# atmel-7-segment-rtc.net
KiCad netlist of a schematic drawn in EAGLE
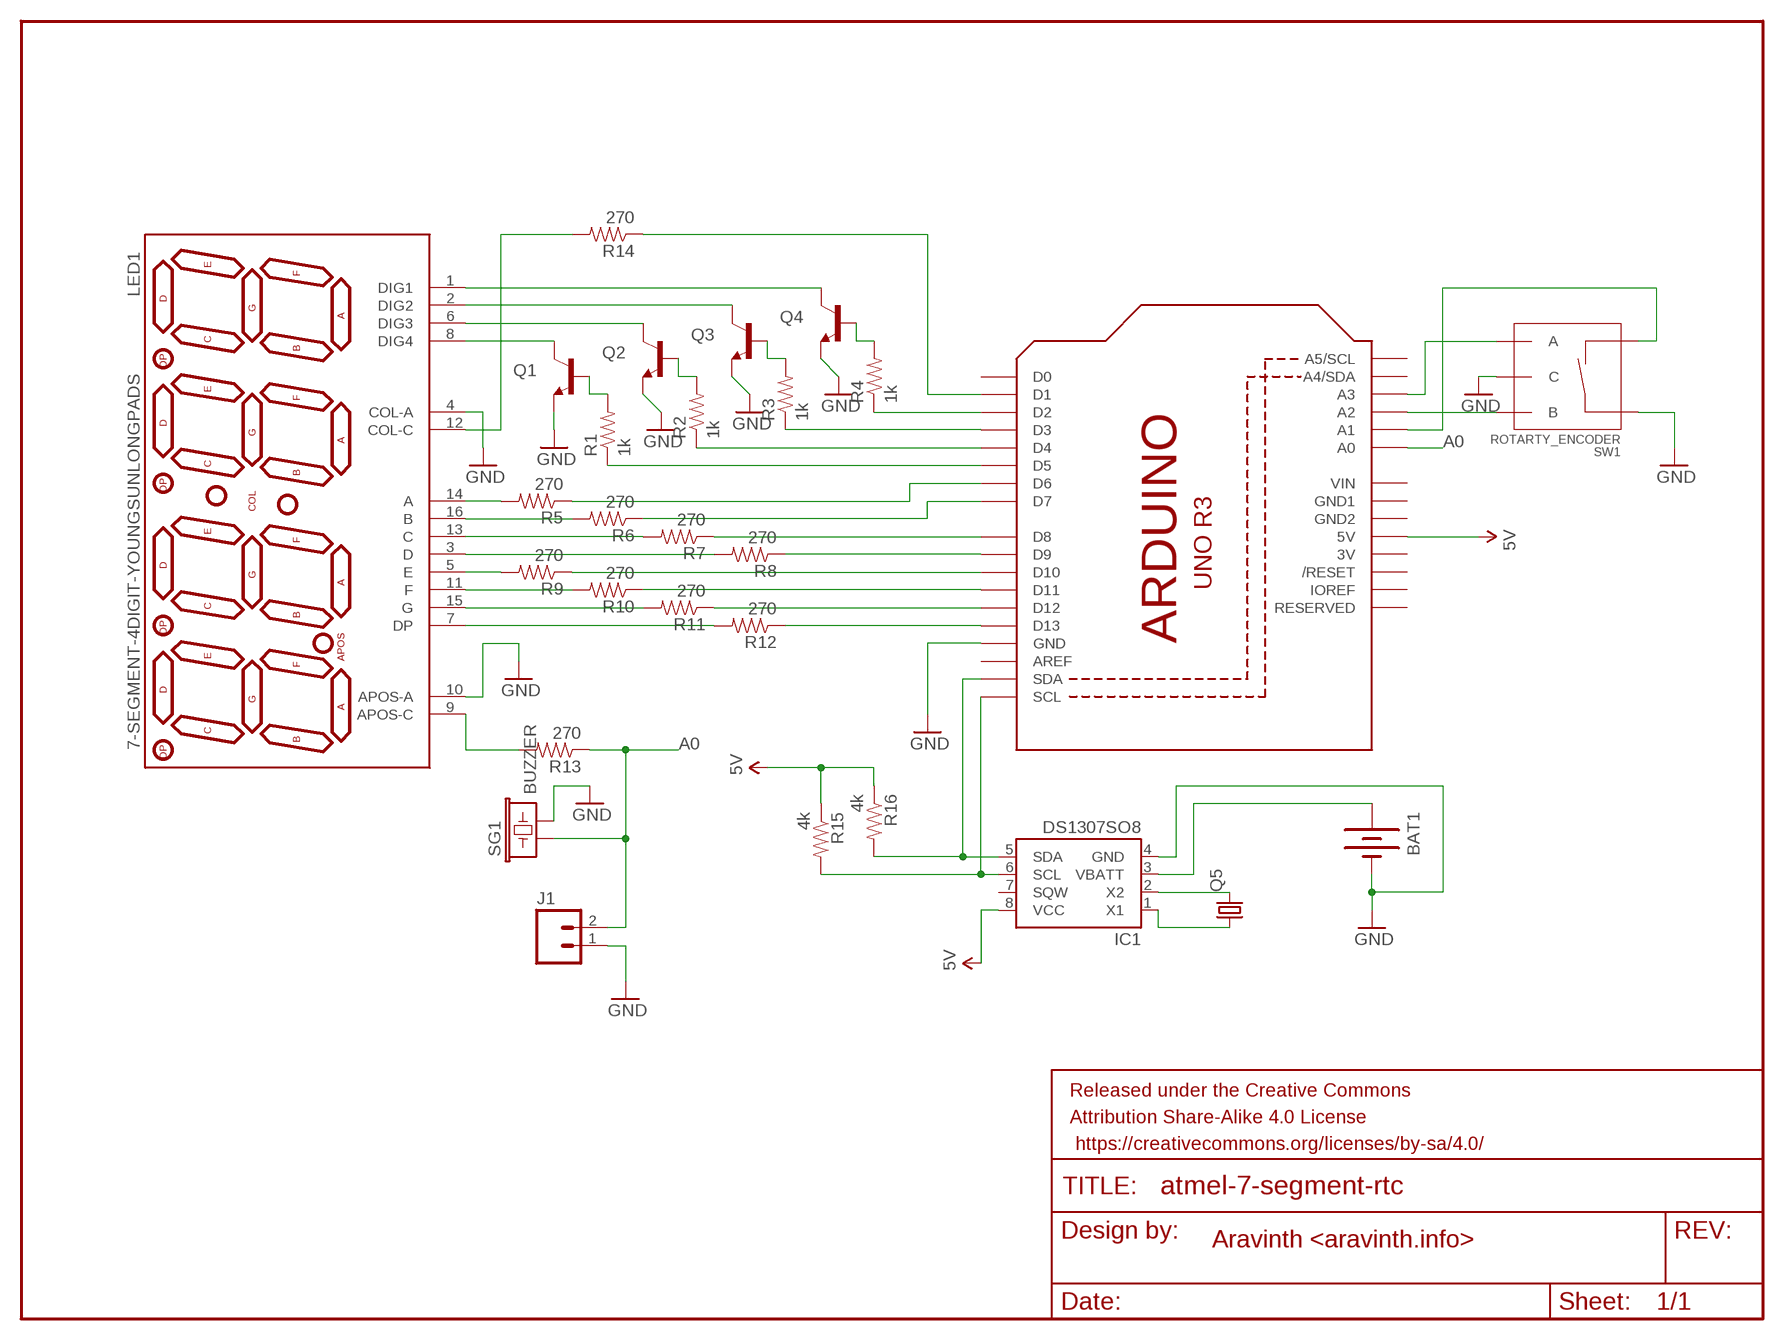
[diagram p0: schematic, sheet 1]

(export (version "E")
  (design (tool "Eeschema 10.0.6"))
  (components
    (comp (ref "ARDUINO")
      (value "ARDUINOR3-DIMENSION")
      (footprint "eagle-import:ARDUINOR3")
      (libsource (lib "eagle-import") (part "ARDUINOR3-DIMENSION"))
    )
    (comp (ref "BAT1")
      (value "BATTERY12MM")
      (footprint "eagle-import:BATTCON_12MM")
      (libsource (lib "eagle-import") (part "BATTERY12MM"))
    )
    (comp (ref "FRAME1")
      (value "FRAME-LETTER")
      (footprint "eagle-import:CREATIVE_COMMONS")
      (libsource (lib "eagle-import") (part "FRAME-LETTER"))
    )
    (comp (ref "IC1")
      (value "DS1307SO8")
      (footprint "eagle-import:SO08")
      (libsource (lib "eagle-import") (part "DS1307SO8"))
    )
    (comp (ref "J1")
      (value "M023.5MM")
      (footprint "eagle-import:SCREWTERMINAL-3.5MM-2")
      (libsource (lib "eagle-import") (part "M023.5MM"))
    )
    (comp (ref "LED1")
      (value "7-SEGMENT-4DIGIT-YOUNGSUNLONGPADS")
      (footprint "eagle-import:7-SEGMENT-4DIGIT-YOUNGSUN-LONGPADS")
      (libsource (lib "eagle-import") (part "7-SEGMENT-4DIGIT-YOUNGSUNLONGPADS"))
    )
    (comp (ref "Q1")
      (value "TRANSISTOR_NPNMMBT2222A")
      (footprint "eagle-import:SOT23-3")
      (libsource (lib "eagle-import") (part "TRANSISTOR_NPNMMBT2222A"))
    )
    (comp (ref "Q2")
      (value "TRANSISTOR_NPNMMBT2222A")
      (footprint "eagle-import:SOT23-3")
      (libsource (lib "eagle-import") (part "TRANSISTOR_NPNMMBT2222A"))
    )
    (comp (ref "Q3")
      (value "TRANSISTOR_NPNMMBT2222A")
      (footprint "eagle-import:SOT23-3")
      (libsource (lib "eagle-import") (part "TRANSISTOR_NPNMMBT2222A"))
    )
    (comp (ref "Q4")
      (value "TRANSISTOR_NPNMMBT2222A")
      (footprint "eagle-import:SOT23-3")
      (libsource (lib "eagle-import") (part "TRANSISTOR_NPNMMBT2222A"))
    )
    (comp (ref "Q5")
      (value "CRYSTALTC26H")
      (footprint "eagle-import:TC26H")
      (libsource (lib "eagle-import") (part "CRYSTALTC26H"))
    )
    (comp (ref "R1")
      (value "1k")
      (footprint "eagle-import:0805")
      (libsource (lib "eagle-import") (part "RESISTOR0805-RES"))
    )
    (comp (ref "R2")
      (value "1k")
      (footprint "eagle-import:0805")
      (libsource (lib "eagle-import") (part "RESISTOR0805-RES"))
    )
    (comp (ref "R3")
      (value "1k")
      (footprint "eagle-import:0805")
      (libsource (lib "eagle-import") (part "RESISTOR0805-RES"))
    )
    (comp (ref "R4")
      (value "1k")
      (footprint "eagle-import:0805")
      (libsource (lib "eagle-import") (part "RESISTOR0805-RES"))
    )
    (comp (ref "R5")
      (value "270")
      (footprint "eagle-import:0805")
      (libsource (lib "eagle-import") (part "RESISTOR0805-RES"))
    )
    (comp (ref "R6")
      (value "270")
      (footprint "eagle-import:0805")
      (libsource (lib "eagle-import") (part "RESISTOR0805-RES"))
    )
    (comp (ref "R7")
      (value "270")
      (footprint "eagle-import:0805")
      (libsource (lib "eagle-import") (part "RESISTOR0805-RES"))
    )
    (comp (ref "R8")
      (value "270")
      (footprint "eagle-import:0805")
      (libsource (lib "eagle-import") (part "RESISTOR0805-RES"))
    )
    (comp (ref "R9")
      (value "270")
      (footprint "eagle-import:0805")
      (libsource (lib "eagle-import") (part "RESISTOR0805-RES"))
    )
    (comp (ref "R10")
      (value "270")
      (footprint "eagle-import:0805")
      (libsource (lib "eagle-import") (part "RESISTOR0805-RES"))
    )
    (comp (ref "R11")
      (value "270")
      (footprint "eagle-import:0805")
      (libsource (lib "eagle-import") (part "RESISTOR0805-RES"))
    )
    (comp (ref "R12")
      (value "270")
      (footprint "eagle-import:0805")
      (libsource (lib "eagle-import") (part "RESISTOR0805-RES"))
    )
    (comp (ref "R13")
      (value "270")
      (footprint "eagle-import:0805")
      (libsource (lib "eagle-import") (part "RESISTOR0805-RES"))
    )
    (comp (ref "R14")
      (value "270")
      (footprint "eagle-import:0805")
      (libsource (lib "eagle-import") (part "RESISTOR0805-RES"))
    )
    (comp (ref "R15")
      (value "4k")
      (footprint "eagle-import:0805")
      (libsource (lib "eagle-import") (part "RESISTOR0805-RES"))
    )
    (comp (ref "R16")
      (value "4k")
      (footprint "eagle-import:0805")
      (libsource (lib "eagle-import") (part "RESISTOR0805-RES"))
    )
    (comp (ref "SG1")
      (value "BUZZER")
      (footprint "eagle-import:BUZZER-12MM-NS")
      (libsource (lib "eagle-import") (part "BUZZERNS"))
    )
    (comp (ref "SW1")
      (value "ROTARTY_ENCODER")
      (footprint "eagle-import:ROTARY_ENC_PLAIN")
      (libsource (lib "eagle-import") (part "ROTARTY_ENCODER"))
    )
  )
  (nets
    (net (code "1") (name "/3V") (class "Default")
      (node (ref "ARDUINO") (pin "3V") (pinfunction "3V_3V") (pintype "power_in"))
    )
    (net (code "2") (name "/A0") (class "Default")
      (node (ref "ARDUINO") (pin "A0") (pinfunction "A0_A0") (pintype "bidirectional"))
      (node (ref "J1") (pin "2") (pinfunction "2_2") (pintype "passive"))
      (node (ref "R13") (pin "1") (pinfunction "1_1") (pintype "passive"))
      (node (ref "SG1") (pin "+") (pinfunction "1_+") (pintype "passive"))
    )
    (net (code "3") (name "/GND1") (class "Default")
      (node (ref "ARDUINO") (pin "GND1") (pinfunction "GND1_GND1") (pintype "power_in"))
    )
    (net (code "4") (name "/GND2") (class "Default")
      (node (ref "ARDUINO") (pin "GND2") (pinfunction "GND2_GND2") (pintype "power_in"))
    )
    (net (code "5") (name "/VIN") (class "Default")
      (node (ref "ARDUINO") (pin "VIN") (pinfunction "VIN_VIN") (pintype "power_in"))
    )
    (net (code "6") (name "5V") (class "Default")
      (node (ref "ARDUINO") (pin "5V") (pinfunction "5V_5V") (pintype "power_in"))
      (node (ref "IC1") (pin "8") (pinfunction "VCC_8") (pintype "bidirectional"))
      (node (ref "R15") (pin "1") (pinfunction "1_1") (pintype "passive"))
      (node (ref "R16") (pin "1") (pinfunction "1_1") (pintype "passive"))
    )
    (net (code "7") (name "GND") (class "Default")
      (node (ref "ARDUINO") (pin "GND") (pinfunction "GND_GND") (pintype "power_in"))
      (node (ref "BAT1") (pin "GND") (pinfunction "-_GND") (pintype "power_in"))
      (node (ref "IC1") (pin "4") (pinfunction "GND_4") (pintype "bidirectional"))
      (node (ref "J1") (pin "1") (pinfunction "1_1") (pintype "passive"))
      (node (ref "LED1") (pin "10") (pinfunction "APOS-A_10") (pintype "bidirectional"))
      (node (ref "LED1") (pin "4") (pinfunction "COL-A_4") (pintype "bidirectional"))
      (node (ref "Q1") (pin "2") (pinfunction "E_2") (pintype "passive"))
      (node (ref "Q2") (pin "2") (pinfunction "E_2") (pintype "passive"))
      (node (ref "Q3") (pin "2") (pinfunction "E_2") (pintype "passive"))
      (node (ref "Q4") (pin "2") (pinfunction "E_2") (pintype "passive"))
      (node (ref "SG1") (pin "-") (pinfunction "2_-") (pintype "passive"))
      (node (ref "SW1") (pin "C") (pinfunction "C_C") (pintype "bidirectional"))
      (node (ref "SW1") (pin "SW+") (pinfunction "SW+_SW+") (pintype "bidirectional"))
    )
    (net (code "8") (name "Net-(ARDUINO-PadA1)") (class "Default")
      (node (ref "ARDUINO") (pin "A1") (pinfunction "A1_A1") (pintype "bidirectional"))
      (node (ref "SW1") (pin "SW-") (pinfunction "SW-_SW-") (pintype "bidirectional"))
    )
    (net (code "9") (name "Net-(ARDUINO-PadA2)") (class "Default")
      (node (ref "ARDUINO") (pin "A2") (pinfunction "A2_A2") (pintype "bidirectional"))
      (node (ref "SW1") (pin "B") (pinfunction "B_B") (pintype "bidirectional"))
    )
    (net (code "10") (name "Net-(ARDUINO-PadA3)") (class "Default")
      (node (ref "ARDUINO") (pin "A3") (pinfunction "A3_A3") (pintype "bidirectional"))
      (node (ref "SW1") (pin "A") (pinfunction "A_A") (pintype "bidirectional"))
    )
    (net (code "11") (name "Net-(ARDUINO-PadD1)") (class "Default")
      (node (ref "ARDUINO") (pin "D1") (pinfunction "D1_D1") (pintype "bidirectional"))
      (node (ref "R14") (pin "1") (pinfunction "1_1") (pintype "passive"))
    )
    (net (code "12") (name "Net-(ARDUINO-PadD2)") (class "Default")
      (node (ref "ARDUINO") (pin "D2") (pinfunction "D2_D2") (pintype "bidirectional"))
      (node (ref "R4") (pin "1") (pinfunction "1_1") (pintype "passive"))
    )
    (net (code "13") (name "Net-(ARDUINO-PadD3)") (class "Default")
      (node (ref "ARDUINO") (pin "D3") (pinfunction "D3_D3") (pintype "bidirectional"))
      (node (ref "R3") (pin "1") (pinfunction "1_1") (pintype "passive"))
    )
    (net (code "14") (name "Net-(ARDUINO-PadD4)") (class "Default")
      (node (ref "ARDUINO") (pin "D4") (pinfunction "D4_D4") (pintype "bidirectional"))
      (node (ref "R2") (pin "1") (pinfunction "1_1") (pintype "passive"))
    )
    (net (code "15") (name "Net-(ARDUINO-PadD5)") (class "Default")
      (node (ref "ARDUINO") (pin "D5") (pinfunction "D5_D5") (pintype "bidirectional"))
      (node (ref "R1") (pin "1") (pinfunction "1_1") (pintype "passive"))
    )
    (net (code "16") (name "Net-(ARDUINO-PadD6)") (class "Default")
      (node (ref "ARDUINO") (pin "D6") (pinfunction "D6_D6") (pintype "bidirectional"))
      (node (ref "R5") (pin "1") (pinfunction "1_1") (pintype "passive"))
    )
    (net (code "17") (name "Net-(ARDUINO-PadD7)") (class "Default")
      (node (ref "ARDUINO") (pin "D7") (pinfunction "D7_D7") (pintype "bidirectional"))
      (node (ref "R6") (pin "1") (pinfunction "1_1") (pintype "passive"))
    )
    (net (code "18") (name "Net-(ARDUINO-PadD8)") (class "Default")
      (node (ref "ARDUINO") (pin "D8") (pinfunction "D8_D8") (pintype "bidirectional"))
      (node (ref "R7") (pin "1") (pinfunction "1_1") (pintype "passive"))
    )
    (net (code "19") (name "Net-(ARDUINO-PadD9)") (class "Default")
      (node (ref "ARDUINO") (pin "D9") (pinfunction "D9_D9") (pintype "bidirectional"))
      (node (ref "R8") (pin "1") (pinfunction "1_1") (pintype "passive"))
    )
    (net (code "20") (name "Net-(ARDUINO-PadD10)") (class "Default")
      (node (ref "ARDUINO") (pin "D10") (pinfunction "D10_D10") (pintype "bidirectional"))
      (node (ref "R9") (pin "1") (pinfunction "1_1") (pintype "passive"))
    )
    (net (code "21") (name "Net-(ARDUINO-PadD11)") (class "Default")
      (node (ref "ARDUINO") (pin "D11") (pinfunction "D11_D11") (pintype "bidirectional"))
      (node (ref "R10") (pin "1") (pinfunction "1_1") (pintype "passive"))
    )
    (net (code "22") (name "Net-(ARDUINO-PadD12)") (class "Default")
      (node (ref "ARDUINO") (pin "D12") (pinfunction "D12_D12") (pintype "bidirectional"))
      (node (ref "R11") (pin "1") (pinfunction "1_1") (pintype "passive"))
    )
    (net (code "23") (name "Net-(ARDUINO-PadD13)") (class "Default")
      (node (ref "ARDUINO") (pin "D13") (pinfunction "D13_D13") (pintype "bidirectional"))
      (node (ref "R12") (pin "1") (pinfunction "1_1") (pintype "passive"))
    )
    (net (code "24") (name "Net-(BAT1-+)") (class "Default")
      (node (ref "BAT1") (pin "PWR@1") (pinfunction "+_PWR@1") (pintype "power_in"))
      (node (ref "IC1") (pin "3") (pinfunction "VBATT_3") (pintype "bidirectional"))
    )
    (net (code "25") (name "Net-(IC1-SCL)") (class "Default")
      (node (ref "ARDUINO") (pin "SCL") (pinfunction "SCL_SCL") (pintype "bidirectional"))
      (node (ref "IC1") (pin "6") (pinfunction "SCL_6") (pintype "bidirectional"))
      (node (ref "R15") (pin "2") (pinfunction "2_2") (pintype "passive"))
    )
    (net (code "26") (name "Net-(IC1-SDA)") (class "Default")
      (node (ref "ARDUINO") (pin "SDA") (pinfunction "SDA_SDA") (pintype "bidirectional"))
      (node (ref "IC1") (pin "5") (pinfunction "SDA_5") (pintype "bidirectional"))
      (node (ref "R16") (pin "2") (pinfunction "2_2") (pintype "passive"))
    )
    (net (code "27") (name "Net-(IC1-X1)") (class "Default")
      (node (ref "IC1") (pin "1") (pinfunction "X1_1") (pintype "bidirectional"))
      (node (ref "Q5") (pin "1") (pinfunction "1_1") (pintype "passive"))
    )
    (net (code "28") (name "Net-(IC1-X2)") (class "Default")
      (node (ref "IC1") (pin "2") (pinfunction "X2_2") (pintype "bidirectional"))
      (node (ref "Q5") (pin "2") (pinfunction "2_2") (pintype "passive"))
    )
    (net (code "29") (name "Net-(LED1-A)") (class "Default")
      (node (ref "LED1") (pin "14") (pinfunction "A_14") (pintype "bidirectional"))
      (node (ref "R5") (pin "2") (pinfunction "2_2") (pintype "passive"))
    )
    (net (code "30") (name "Net-(LED1-APOS-C)") (class "Default")
      (node (ref "LED1") (pin "9") (pinfunction "APOS-C_9") (pintype "bidirectional"))
      (node (ref "R13") (pin "2") (pinfunction "2_2") (pintype "passive"))
    )
    (net (code "31") (name "Net-(LED1-B)") (class "Default")
      (node (ref "LED1") (pin "16") (pinfunction "B_16") (pintype "bidirectional"))
      (node (ref "R6") (pin "2") (pinfunction "2_2") (pintype "passive"))
    )
    (net (code "32") (name "Net-(LED1-C)") (class "Default")
      (node (ref "LED1") (pin "13") (pinfunction "C_13") (pintype "bidirectional"))
      (node (ref "R7") (pin "2") (pinfunction "2_2") (pintype "passive"))
    )
    (net (code "33") (name "Net-(LED1-COL-C)") (class "Default")
      (node (ref "LED1") (pin "12") (pinfunction "COL-C_12") (pintype "bidirectional"))
      (node (ref "R14") (pin "2") (pinfunction "2_2") (pintype "passive"))
    )
    (net (code "34") (name "Net-(LED1-D)") (class "Default")
      (node (ref "LED1") (pin "3") (pinfunction "D_3") (pintype "bidirectional"))
      (node (ref "R8") (pin "2") (pinfunction "2_2") (pintype "passive"))
    )
    (net (code "35") (name "Net-(LED1-DIG1)") (class "Default")
      (node (ref "LED1") (pin "1") (pinfunction "DIG1_1") (pintype "bidirectional"))
      (node (ref "Q4") (pin "3") (pinfunction "C_3") (pintype "passive"))
    )
    (net (code "36") (name "Net-(LED1-DIG2)") (class "Default")
      (node (ref "LED1") (pin "2") (pinfunction "DIG2_2") (pintype "bidirectional"))
      (node (ref "Q3") (pin "3") (pinfunction "C_3") (pintype "passive"))
    )
    (net (code "37") (name "Net-(LED1-DIG3)") (class "Default")
      (node (ref "LED1") (pin "6") (pinfunction "DIG3_6") (pintype "bidirectional"))
      (node (ref "Q2") (pin "3") (pinfunction "C_3") (pintype "passive"))
    )
    (net (code "38") (name "Net-(LED1-DIG4)") (class "Default")
      (node (ref "LED1") (pin "8") (pinfunction "DIG4_8") (pintype "bidirectional"))
      (node (ref "Q1") (pin "3") (pinfunction "C_3") (pintype "passive"))
    )
    (net (code "39") (name "Net-(LED1-DP)") (class "Default")
      (node (ref "LED1") (pin "7") (pinfunction "DP_7") (pintype "bidirectional"))
      (node (ref "R12") (pin "2") (pinfunction "2_2") (pintype "passive"))
    )
    (net (code "40") (name "Net-(LED1-E)") (class "Default")
      (node (ref "LED1") (pin "5") (pinfunction "E_5") (pintype "bidirectional"))
      (node (ref "R9") (pin "2") (pinfunction "2_2") (pintype "passive"))
    )
    (net (code "41") (name "Net-(LED1-F)") (class "Default")
      (node (ref "LED1") (pin "11") (pinfunction "F_11") (pintype "bidirectional"))
      (node (ref "R10") (pin "2") (pinfunction "2_2") (pintype "passive"))
    )
    (net (code "42") (name "Net-(LED1-G)") (class "Default")
      (node (ref "LED1") (pin "15") (pinfunction "G_15") (pintype "bidirectional"))
      (node (ref "R11") (pin "2") (pinfunction "2_2") (pintype "passive"))
    )
    (net (code "43") (name "Net-(Q1-B)") (class "Default")
      (node (ref "Q1") (pin "1") (pinfunction "B_1") (pintype "passive"))
      (node (ref "R1") (pin "2") (pinfunction "2_2") (pintype "passive"))
    )
    (net (code "44") (name "Net-(Q2-B)") (class "Default")
      (node (ref "Q2") (pin "1") (pinfunction "B_1") (pintype "passive"))
      (node (ref "R2") (pin "2") (pinfunction "2_2") (pintype "passive"))
    )
    (net (code "45") (name "Net-(Q3-B)") (class "Default")
      (node (ref "Q3") (pin "1") (pinfunction "B_1") (pintype "passive"))
      (node (ref "R3") (pin "2") (pinfunction "2_2") (pintype "passive"))
    )
    (net (code "46") (name "Net-(Q4-B)") (class "Default")
      (node (ref "Q4") (pin "1") (pinfunction "B_1") (pintype "passive"))
      (node (ref "R4") (pin "2") (pinfunction "2_2") (pintype "passive"))
    )
    (net (code "47") (name "unconnected-(ARDUINO-A4{slash}SDA-PadA4)") (class "Default")
      (node (ref "ARDUINO") (pin "A4") (pinfunction "A4/SDA_A4") (pintype "bidirectional"))
    )
    (net (code "48") (name "unconnected-(ARDUINO-A5{slash}SCL-PadA5)") (class "Default")
      (node (ref "ARDUINO") (pin "A5") (pinfunction "A5/SCL_A5") (pintype "bidirectional"))
    )
    (net (code "49") (name "unconnected-(ARDUINO-PadAREF)") (class "Default")
      (node (ref "ARDUINO") (pin "AREF") (pinfunction "AREF_AREF") (pintype "bidirectional"))
    )
    (net (code "50") (name "unconnected-(ARDUINO-PadD0)") (class "Default")
      (node (ref "ARDUINO") (pin "D0") (pinfunction "D0_D0") (pintype "bidirectional"))
    )
    (net (code "51") (name "unconnected-(ARDUINO-PadIOREF)") (class "Default")
      (node (ref "ARDUINO") (pin "IOREF") (pinfunction "IOREF_IOREF") (pintype "output"))
    )
    (net (code "52") (name "unconnected-(ARDUINO-PadRESERVED)") (class "Default")
      (node (ref "ARDUINO") (pin "RESERVED") (pinfunction "RESERVED_RESERVED") (pintype "no_connect"))
    )
    (net (code "53") (name "unconnected-(ARDUINO-{slash}RESET-PadRESET)") (class "Default")
      (node (ref "ARDUINO") (pin "RESET") (pinfunction "/RESET_RESET") (pintype "bidirectional"))
    )
    (net (code "54") (name "unconnected-(IC1-SQW-Pad7)") (class "Default")
      (node (ref "IC1") (pin "7") (pinfunction "SQW_7") (pintype "bidirectional"))
    )
  )
)
